# Spring2020V1_7.net
KiCad netlist of a schematic drawn in EAGLE
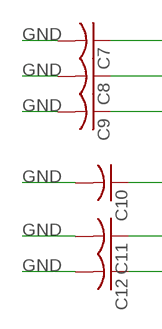
[diagram p0: schematic, sheet 1, part 1 of 2]
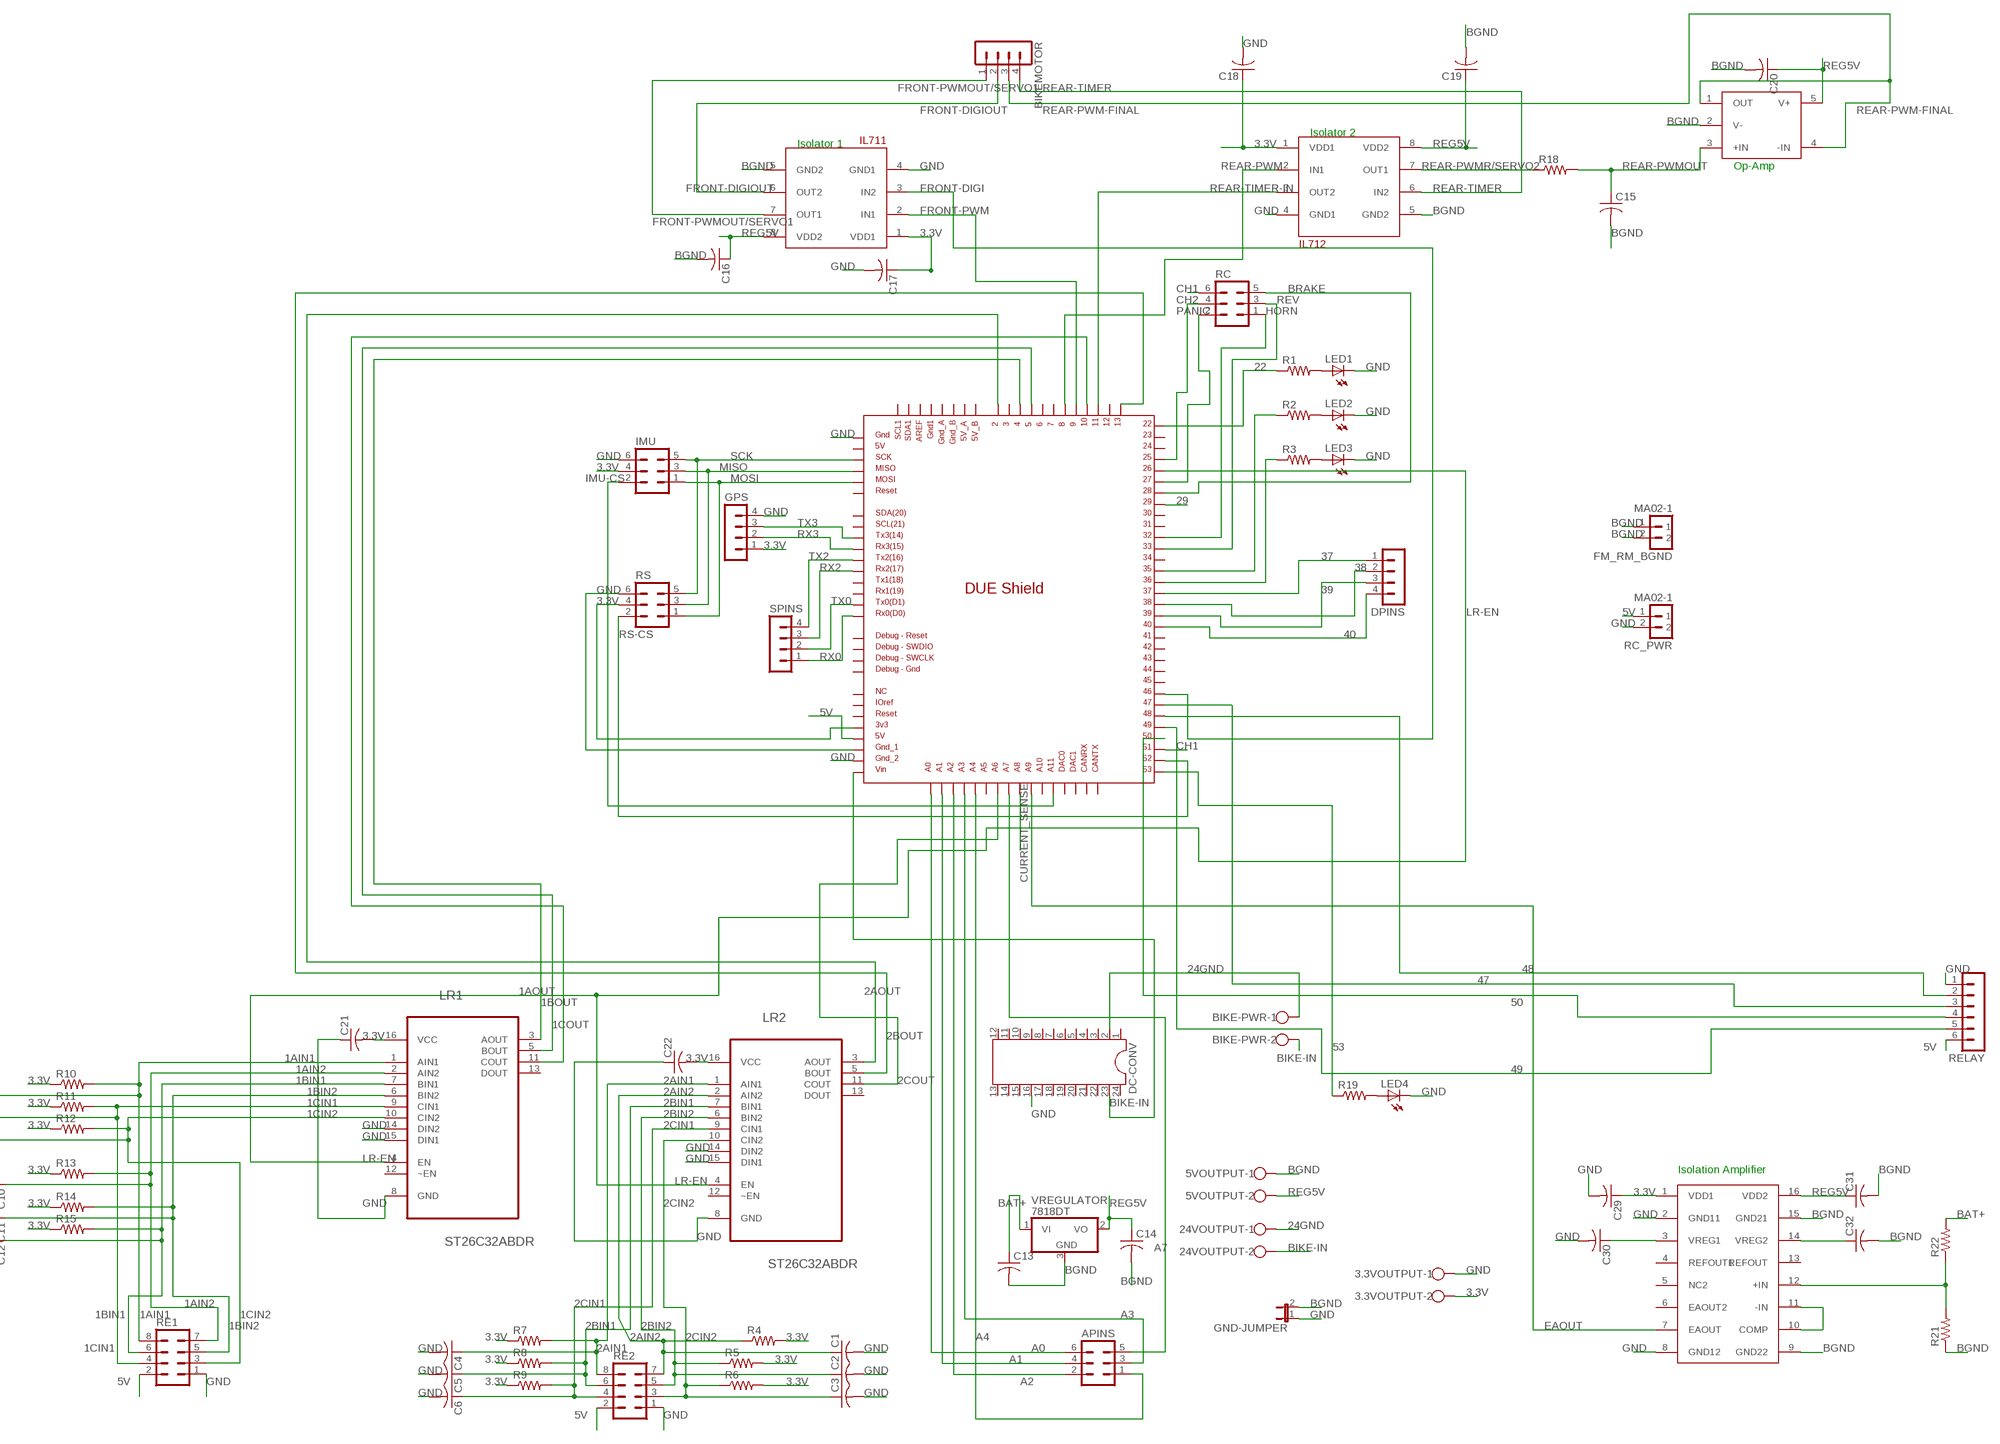
[diagram p1: schematic, sheet 1, part 2 of 2]

(export (version "E")
  (design (tool "Eeschema 10.0.6"))
  (components
    (comp (ref "3.3VOUTPUT")
      (value "W237-102")
      (footprint "eagle-import:W237-102")
      (fields (field (name "MPN") "237-102"))
      (libsource (lib "eagle-import") (part "W237-102"))
    )
    (comp (ref "5VOUTPUT")
      (value "W237-102")
      (footprint "eagle-import:W237-102")
      (fields (field (name "MPN") "237-102"))
      (libsource (lib "eagle-import") (part "W237-102"))
    )
    (comp (ref "24VOUTPUT")
      (value "W237-102")
      (footprint "eagle-import:W237-102")
      (fields (field (name "MPN") "237-102"))
      (libsource (lib "eagle-import") (part "W237-102"))
    )
    (comp (ref "APINS")
      (value "MA03-2")
      (footprint "eagle-import:MA03-2")
      (libsource (lib "eagle-import") (part "MA03-2"))
    )
    (comp (ref "BIKE-PWR")
      (value "W237-102")
      (footprint "eagle-import:W237-102")
      (fields (field (name "MPN") "237-102"))
      (libsource (lib "eagle-import") (part "W237-102"))
    )
    (comp (ref "BIKEMOTOR")
      (value "MA04-1")
      (footprint "eagle-import:MA04-1")
      (libsource (lib "eagle-import") (part "MA04-1"))
    )
    (comp (ref "C1")
      (value "C-US025-025X050")
      (footprint "eagle-import:C025-025X050")
      (libsource (lib "eagle-import") (part "C-US025-025X050"))
    )
    (comp (ref "C2")
      (value "C-US025-025X050")
      (footprint "eagle-import:C025-025X050")
      (libsource (lib "eagle-import") (part "C-US025-025X050"))
    )
    (comp (ref "C3")
      (value "C-US025-025X050")
      (footprint "eagle-import:C025-025X050")
      (libsource (lib "eagle-import") (part "C-US025-025X050"))
    )
    (comp (ref "C4")
      (value "C-US025-025X050")
      (footprint "eagle-import:C025-025X050")
      (libsource (lib "eagle-import") (part "C-US025-025X050"))
    )
    (comp (ref "C5")
      (value "C-US025-025X050")
      (footprint "eagle-import:C025-025X050")
      (libsource (lib "eagle-import") (part "C-US025-025X050"))
    )
    (comp (ref "C6")
      (value "C-US025-025X050")
      (footprint "eagle-import:C025-025X050")
      (libsource (lib "eagle-import") (part "C-US025-025X050"))
    )
    (comp (ref "C7")
      (value "C-US025-025X050")
      (footprint "eagle-import:C025-025X050")
      (libsource (lib "eagle-import") (part "C-US025-025X050"))
    )
    (comp (ref "C8")
      (value "C-US025-025X050")
      (footprint "eagle-import:C025-025X050")
      (libsource (lib "eagle-import") (part "C-US025-025X050"))
    )
    (comp (ref "C9")
      (value "C-US025-025X050")
      (footprint "eagle-import:C025-025X050")
      (libsource (lib "eagle-import") (part "C-US025-025X050"))
    )
    (comp (ref "C10")
      (value "C-US025-025X050")
      (footprint "eagle-import:C025-025X050")
      (libsource (lib "eagle-import") (part "C-US025-025X050"))
    )
    (comp (ref "C11")
      (value "C-US025-025X050")
      (footprint "eagle-import:C025-025X050")
      (libsource (lib "eagle-import") (part "C-US025-025X050"))
    )
    (comp (ref "C12")
      (value "C-US025-025X050")
      (footprint "eagle-import:C025-025X050")
      (libsource (lib "eagle-import") (part "C-US025-025X050"))
    )
    (comp (ref "C13")
      (value "C-US025-050X050")
      (footprint "eagle-import:C025-050X050")
      (libsource (lib "eagle-import") (part "C-US025-050X050"))
    )
    (comp (ref "C14")
      (value "C-US025-050X050")
      (footprint "eagle-import:C025-050X050")
      (libsource (lib "eagle-import") (part "C-US025-050X050"))
    )
    (comp (ref "C15")
      (value "C-US025-050X050")
      (footprint "eagle-import:C025-050X050")
      (libsource (lib "eagle-import") (part "C-US025-050X050"))
    )
    (comp (ref "C16")
      (value "C-US025-050X050")
      (footprint "eagle-import:C025-050X050")
      (libsource (lib "eagle-import") (part "C-US025-050X050"))
    )
    (comp (ref "C17")
      (value "C-US025-050X050")
      (footprint "eagle-import:C025-050X050")
      (libsource (lib "eagle-import") (part "C-US025-050X050"))
    )
    (comp (ref "C18")
      (value "C-US025-050X050")
      (footprint "eagle-import:C025-050X050")
      (libsource (lib "eagle-import") (part "C-US025-050X050"))
    )
    (comp (ref "C19")
      (value "C-US025-050X050")
      (footprint "eagle-import:C025-050X050")
      (libsource (lib "eagle-import") (part "C-US025-050X050"))
    )
    (comp (ref "C20")
      (value "C-US025-050X050")
      (footprint "eagle-import:C025-050X050")
      (libsource (lib "eagle-import") (part "C-US025-050X050"))
    )
    (comp (ref "C21")
      (value "C-US025-050X050")
      (footprint "eagle-import:C025-050X050")
      (libsource (lib "eagle-import") (part "C-US025-050X050"))
    )
    (comp (ref "C22")
      (value "C-US025-050X050")
      (footprint "eagle-import:C025-050X050")
      (libsource (lib "eagle-import") (part "C-US025-050X050"))
    )
    (comp (ref "C29")
      (value "C-US025-050X050")
      (footprint "eagle-import:C025-050X050")
      (libsource (lib "eagle-import") (part "C-US025-050X050"))
    )
    (comp (ref "C30")
      (value "C-US025-050X050")
      (footprint "eagle-import:C025-050X050")
      (libsource (lib "eagle-import") (part "C-US025-050X050"))
    )
    (comp (ref "C31")
      (value "C-US025-050X050")
      (footprint "eagle-import:C025-050X050")
      (libsource (lib "eagle-import") (part "C-US025-050X050"))
    )
    (comp (ref "C32")
      (value "C-US025-050X050")
      (footprint "eagle-import:C025-050X050")
      (libsource (lib "eagle-import") (part "C-US025-050X050"))
    )
    (comp (ref "DC-CONV")
      (value "CU.INC---VAWQ6-Q48-S12H-6")
      (footprint "eagle-import:DIL24-6")
      (libsource (lib "eagle-import") (part "CU.INC---VAWQ6-Q48-S12H-6"))
    )
    (comp (ref "DPINS")
      (value "MA04-1")
      (footprint "eagle-import:MA04-1")
      (libsource (lib "eagle-import") (part "MA04-1"))
    )
    (comp (ref "FM_RM_BGND")
      (value "MA02-1")
      (footprint "eagle-import:MA02-1")
      (libsource (lib "eagle-import") (part "MA02-1"))
    )
    (comp (ref "GND-JUMPER")
      (value "JP1E")
      (footprint "eagle-import:JP1")
      (libsource (lib "eagle-import") (part "JP1E"))
    )
    (comp (ref "GPS")
      (value "MA04-1")
      (footprint "eagle-import:MA04-1")
      (libsource (lib "eagle-import") (part "MA04-1"))
    )
    (comp (ref "IMU")
      (value "MA03-2")
      (footprint "eagle-import:MA03-2")
      (libsource (lib "eagle-import") (part "MA03-2"))
    )
    (comp (ref "LED1")
      (value "LED5MM")
      (footprint "eagle-import:LED5MM")
      (libsource (lib "eagle-import") (part "LED5MM"))
    )
    (comp (ref "LED2")
      (value "LED5MM")
      (footprint "eagle-import:LED5MM")
      (libsource (lib "eagle-import") (part "LED5MM"))
    )
    (comp (ref "LED3")
      (value "LED5MM")
      (footprint "eagle-import:LED5MM")
      (libsource (lib "eagle-import") (part "LED5MM"))
    )
    (comp (ref "LED4")
      (value "LED5MM")
      (footprint "eagle-import:LED5MM")
      (libsource (lib "eagle-import") (part "LED5MM"))
    )
    (comp (ref "LR1")
      (value "ST26C32ABDR")
      (footprint "eagle-import:SOIC127P600X175-16N")
      (libsource (lib "eagle-import") (part "ST26C32ABDR"))
    )
    (comp (ref "LR2")
      (value "ST26C32ABDR")
      (footprint "eagle-import:SOIC127P600X175-16N")
      (libsource (lib "eagle-import") (part "ST26C32ABDR"))
    )
    (comp (ref "OP-AMP")
      (value "OPAMP")
      (footprint "eagle-import:SOT95P280X145-5N")
      (libsource (lib "eagle-import") (part "OPAMP"))
    )
    (comp (ref "R1")
      (value "R-US_0309/10")
      (footprint "eagle-import:0309_10")
      (libsource (lib "eagle-import") (part "R-US_0309/10"))
    )
    (comp (ref "R2")
      (value "R-US_0309/10")
      (footprint "eagle-import:0309_10")
      (libsource (lib "eagle-import") (part "R-US_0309/10"))
    )
    (comp (ref "R3")
      (value "R-US_0309/10")
      (footprint "eagle-import:0309_10")
      (libsource (lib "eagle-import") (part "R-US_0309/10"))
    )
    (comp (ref "R4")
      (value "R-US_0613/15")
      (footprint "eagle-import:P0613_15")
      (libsource (lib "eagle-import") (part "resistor_R-US_0613/15"))
    )
    (comp (ref "R5")
      (value "R-US_0613/15")
      (footprint "eagle-import:P0613_15")
      (libsource (lib "eagle-import") (part "resistor_R-US_0613/15"))
    )
    (comp (ref "R6")
      (value "R-US_0613/15")
      (footprint "eagle-import:P0613_15")
      (libsource (lib "eagle-import") (part "resistor_R-US_0613/15"))
    )
    (comp (ref "R7")
      (value "R-US_0613/15")
      (footprint "eagle-import:P0613_15")
      (libsource (lib "eagle-import") (part "resistor_R-US_0613/15"))
    )
    (comp (ref "R8")
      (value "R-US_0613/15")
      (footprint "eagle-import:P0613_15")
      (libsource (lib "eagle-import") (part "resistor_R-US_0613/15"))
    )
    (comp (ref "R9")
      (value "R-US_0613/15")
      (footprint "eagle-import:P0613_15")
      (libsource (lib "eagle-import") (part "resistor_R-US_0613/15"))
    )
    (comp (ref "R10")
      (value "R-US_0613/15")
      (footprint "eagle-import:P0613_15")
      (libsource (lib "eagle-import") (part "resistor_R-US_0613/15"))
    )
    (comp (ref "R11")
      (value "R-US_0613/15")
      (footprint "eagle-import:P0613_15")
      (libsource (lib "eagle-import") (part "resistor_R-US_0613/15"))
    )
    (comp (ref "R12")
      (value "R-US_0613/15")
      (footprint "eagle-import:P0613_15")
      (libsource (lib "eagle-import") (part "resistor_R-US_0613/15"))
    )
    (comp (ref "R13")
      (value "R-US_0613/15")
      (footprint "eagle-import:P0613_15")
      (libsource (lib "eagle-import") (part "resistor_R-US_0613/15"))
    )
    (comp (ref "R14")
      (value "R-US_0613/15")
      (footprint "eagle-import:P0613_15")
      (libsource (lib "eagle-import") (part "resistor_R-US_0613/15"))
    )
    (comp (ref "R15")
      (value "R-US_0613/15")
      (footprint "eagle-import:P0613_15")
      (libsource (lib "eagle-import") (part "resistor_R-US_0613/15"))
    )
    (comp (ref "R18")
      (value "R-US_0414/15")
      (footprint "eagle-import:0414_15")
      (libsource (lib "eagle-import") (part "resistor_R-US_0414/15"))
    )
    (comp (ref "R19")
      (value "R-US_0309/10")
      (footprint "eagle-import:0309_10")
      (libsource (lib "eagle-import") (part "R-US_0309/10"))
    )
    (comp (ref "R21")
      (value "R-US_0414/15")
      (footprint "eagle-import:0414_15")
      (libsource (lib "eagle-import") (part "resistor_R-US_0414/15"))
    )
    (comp (ref "R22")
      (value "R-US_0414/15")
      (footprint "eagle-import:0414_15")
      (libsource (lib "eagle-import") (part "resistor_R-US_0414/15"))
    )
    (comp (ref "RC")
      (value "MA03-2")
      (footprint "eagle-import:MA03-2")
      (libsource (lib "eagle-import") (part "MA03-2"))
    )
    (comp (ref "RC_PWR")
      (value "MA02-1")
      (footprint "eagle-import:MA02-1")
      (libsource (lib "eagle-import") (part "MA02-1"))
    )
    (comp (ref "RE1")
      (value "MA04-2")
      (footprint "eagle-import:MA04-2")
      (libsource (lib "eagle-import") (part "MA04-2"))
    )
    (comp (ref "RE2")
      (value "MA04-2")
      (footprint "eagle-import:MA04-2")
      (libsource (lib "eagle-import") (part "MA04-2"))
    )
    (comp (ref "RELAY")
      (value "MA06-1")
      (footprint "eagle-import:MA06-1")
      (libsource (lib "eagle-import") (part "MA06-1"))
    )
    (comp (ref "RS")
      (value "MA03-2")
      (footprint "eagle-import:MA03-2")
      (libsource (lib "eagle-import") (part "MA03-2"))
    )
    (comp (ref "SPINS")
      (value "MA04-1")
      (footprint "eagle-import:MA04-1")
      (libsource (lib "eagle-import") (part "MA04-1"))
    )
    (comp (ref "U$1")
      (value "DUE(NORMAL)")
      (footprint "eagle-import:DUE(NORMAL)")
      (libsource (lib "eagle-import") (part "DUE(NORMAL)"))
    )
    (comp (ref "U$2")
      (value "IL-711")
      (footprint "eagle-import:8PINSOIC")
      (libsource (lib "eagle-import") (part "IL-711"))
    )
    (comp (ref "U$5")
      (value "ISOLATED_ERROR_AMP_ADUM3190")
      (footprint "eagle-import:QSOP16")
      (libsource (lib "eagle-import") (part "ISOLATED_ERROR_AMP_ADUM3190"))
    )
    (comp (ref "U$7")
      (value "IL-712")
      (footprint "eagle-import:8PINSOIC")
      (libsource (lib "eagle-import") (part "IL-712"))
    )
    (comp (ref "VREGULATOR")
      (value "7818DT")
      (footprint "eagle-import:TO252")
      (libsource (lib "eagle-import") (part "78DT18"))
    )
  )
  (nets
    (net (code "1") (name "/1AIN1") (class "Default")
      (node (ref "C7") (pin "1") (pinfunction "1_1") (pintype "passive"))
      (node (ref "LR1") (pin "1") (pinfunction "AIN1_1") (pintype "input"))
      (node (ref "R10") (pin "2") (pinfunction "2_2") (pintype "passive"))
      (node (ref "RE1") (pin "8") (pinfunction "8_8") (pintype "passive"))
    )
    (net (code "2") (name "/1AIN2") (class "Default")
      (node (ref "C10") (pin "1") (pinfunction "1_1") (pintype "passive"))
      (node (ref "LR1") (pin "2") (pinfunction "AIN2_2") (pintype "input"))
      (node (ref "R13") (pin "2") (pinfunction "2_2") (pintype "passive"))
      (node (ref "RE1") (pin "7") (pinfunction "7_7") (pintype "passive"))
    )
    (net (code "3") (name "/1AOUT") (class "Default")
      (node (ref "LR1") (pin "3") (pinfunction "AOUT_3") (pintype "output"))
      (node (ref "U$1") (pin "4") (pinfunction "4_4") (pintype "bidirectional"))
    )
    (net (code "4") (name "/1BIN1") (class "Default")
      (node (ref "C12") (pin "1") (pinfunction "1_1") (pintype "passive"))
      (node (ref "LR1") (pin "7") (pinfunction "BIN1_7") (pintype "input"))
      (node (ref "R15") (pin "2") (pinfunction "2_2") (pintype "passive"))
      (node (ref "RE1") (pin "6") (pinfunction "6_6") (pintype "passive"))
    )
    (net (code "5") (name "/1BIN2") (class "Default")
      (node (ref "C11") (pin "1") (pinfunction "1_1") (pintype "passive"))
      (node (ref "LR1") (pin "6") (pinfunction "BIN2_6") (pintype "input"))
      (node (ref "R14") (pin "2") (pinfunction "2_2") (pintype "passive"))
      (node (ref "RE1") (pin "5") (pinfunction "5_5") (pintype "passive"))
    )
    (net (code "6") (name "/1BOUT") (class "Default")
      (node (ref "LR1") (pin "5") (pinfunction "BOUT_5") (pintype "output"))
      (node (ref "U$1") (pin "5") (pinfunction "5_5") (pintype "bidirectional"))
    )
    (net (code "7") (name "/1CIN1") (class "Default")
      (node (ref "C8") (pin "1") (pinfunction "1_1") (pintype "passive"))
      (node (ref "LR1") (pin "9") (pinfunction "CIN1_9") (pintype "input"))
      (node (ref "R11") (pin "2") (pinfunction "2_2") (pintype "passive"))
      (node (ref "RE1") (pin "4") (pinfunction "4_4") (pintype "passive"))
    )
    (net (code "8") (name "/1CIN2") (class "Default")
      (node (ref "C9") (pin "1") (pinfunction "1_1") (pintype "passive"))
      (node (ref "LR1") (pin "10") (pinfunction "CIN2_10") (pintype "input"))
      (node (ref "R12") (pin "2") (pinfunction "2_2") (pintype "passive"))
      (node (ref "RE1") (pin "3") (pinfunction "3_3") (pintype "passive"))
    )
    (net (code "9") (name "/1COUT") (class "Default")
      (node (ref "LR1") (pin "11") (pinfunction "COUT_11") (pintype "output"))
      (node (ref "U$1") (pin "10") (pinfunction "10_10") (pintype "bidirectional"))
    )
    (net (code "10") (name "/2AIN1") (class "Default")
      (node (ref "C4") (pin "1") (pinfunction "1_1") (pintype "passive"))
      (node (ref "LR2") (pin "1") (pinfunction "AIN1_1") (pintype "input"))
      (node (ref "R7") (pin "2") (pinfunction "2_2") (pintype "passive"))
      (node (ref "RE2") (pin "8") (pinfunction "8_8") (pintype "passive"))
    )
    (net (code "11") (name "/2AIN2") (class "Default")
      (node (ref "C1") (pin "1") (pinfunction "1_1") (pintype "passive"))
      (node (ref "LR2") (pin "2") (pinfunction "AIN2_2") (pintype "input"))
      (node (ref "R4") (pin "1") (pinfunction "1_1") (pintype "passive"))
      (node (ref "RE2") (pin "7") (pinfunction "7_7") (pintype "passive"))
    )
    (net (code "12") (name "/2AOUT") (class "Default")
      (node (ref "LR2") (pin "3") (pinfunction "AOUT_3") (pintype "output"))
      (node (ref "U$1") (pin "2") (pinfunction "2_2") (pintype "bidirectional"))
    )
    (net (code "13") (name "/2BIN1") (class "Default")
      (node (ref "C5") (pin "1") (pinfunction "1_1") (pintype "passive"))
      (node (ref "LR2") (pin "7") (pinfunction "BIN1_7") (pintype "input"))
      (node (ref "R8") (pin "2") (pinfunction "2_2") (pintype "passive"))
      (node (ref "RE2") (pin "6") (pinfunction "6_6") (pintype "passive"))
    )
    (net (code "14") (name "/2BIN2") (class "Default")
      (node (ref "C2") (pin "1") (pinfunction "1_1") (pintype "passive"))
      (node (ref "LR2") (pin "6") (pinfunction "BIN2_6") (pintype "input"))
      (node (ref "R5") (pin "1") (pinfunction "1_1") (pintype "passive"))
      (node (ref "RE2") (pin "5") (pinfunction "5_5") (pintype "passive"))
    )
    (net (code "15") (name "/2BOUT") (class "Default")
      (node (ref "LR2") (pin "5") (pinfunction "BOUT_5") (pintype "output"))
      (node (ref "U$1") (pin "13") (pinfunction "13_13") (pintype "bidirectional"))
    )
    (net (code "16") (name "/2CIN1") (class "Default")
      (node (ref "C6") (pin "1") (pinfunction "1_1") (pintype "passive"))
      (node (ref "LR2") (pin "9") (pinfunction "CIN1_9") (pintype "input"))
      (node (ref "R9") (pin "2") (pinfunction "2_2") (pintype "passive"))
      (node (ref "RE2") (pin "4") (pinfunction "4_4") (pintype "passive"))
    )
    (net (code "17") (name "/2CIN2") (class "Default")
      (node (ref "C3") (pin "1") (pinfunction "1_1") (pintype "passive"))
      (node (ref "LR2") (pin "10") (pinfunction "CIN2_10") (pintype "input"))
      (node (ref "R6") (pin "1") (pinfunction "1_1") (pintype "passive"))
      (node (ref "RE2") (pin "3") (pinfunction "3_3") (pintype "passive"))
    )
    (net (code "18") (name "/2COUT") (class "Default")
      (node (ref "LR2") (pin "11") (pinfunction "COUT_11") (pintype "output"))
      (node (ref "U$1") (pin "A6") (pinfunction "A6_A6") (pintype "bidirectional"))
    )
    (net (code "19") (name "/3.3V") (class "Default")
      (node (ref "3.3VOUTPUT") (pin "2") (pinfunction "KL_2") (pintype "passive"))
      (node (ref "C17") (pin "1") (pinfunction "1_1") (pintype "passive"))
      (node (ref "C18") (pin "1") (pinfunction "1_1") (pintype "passive"))
      (node (ref "C21") (pin "2") (pinfunction "2_2") (pintype "passive"))
      (node (ref "C22") (pin "2") (pinfunction "2_2") (pintype "passive"))
      (node (ref "C29") (pin "1") (pinfunction "1_1") (pintype "passive"))
      (node (ref "GPS") (pin "1") (pinfunction "1_1") (pintype "passive"))
      (node (ref "IMU") (pin "4") (pinfunction "4_4") (pintype "passive"))
      (node (ref "LR1") (pin "16") (pinfunction "VCC_16") (pintype "power_in"))
      (node (ref "LR2") (pin "16") (pinfunction "VCC_16") (pintype "power_in"))
      (node (ref "R10") (pin "1") (pinfunction "1_1") (pintype "passive"))
      (node (ref "R11") (pin "1") (pinfunction "1_1") (pintype "passive"))
      (node (ref "R12") (pin "1") (pinfunction "1_1") (pintype "passive"))
      (node (ref "R13") (pin "1") (pinfunction "1_1") (pintype "passive"))
      (node (ref "R14") (pin "1") (pinfunction "1_1") (pintype "passive"))
      (node (ref "R15") (pin "1") (pinfunction "1_1") (pintype "passive"))
      (node (ref "R4") (pin "2") (pinfunction "2_2") (pintype "passive"))
      (node (ref "R5") (pin "2") (pinfunction "2_2") (pintype "passive"))
      (node (ref "R6") (pin "2") (pinfunction "2_2") (pintype "passive"))
      (node (ref "R7") (pin "1") (pinfunction "1_1") (pintype "passive"))
      (node (ref "R8") (pin "1") (pinfunction "1_1") (pintype "passive"))
      (node (ref "R9") (pin "1") (pinfunction "1_1") (pintype "passive"))
      (node (ref "RS") (pin "4") (pinfunction "4_4") (pintype "passive"))
      (node (ref "U$1") (pin "3V3") (pinfunction "3V3_3V3") (pintype "bidirectional"))
      (node (ref "U$2") (pin "1") (pinfunction "VDD1_1") (pintype "power_in"))
      (node (ref "U$5") (pin "1") (pinfunction "VDD1_1") (pintype "bidirectional"))
      (node (ref "U$7") (pin "1") (pinfunction "VDD1_1") (pintype "power_in"))
    )
    (net (code "20") (name "/5V") (class "Default")
      (node (ref "RC_PWR") (pin "1") (pinfunction "1_1") (pintype "passive"))
      (node (ref "RE1") (pin "2") (pinfunction "2_2") (pintype "passive"))
      (node (ref "RE2") (pin "2") (pinfunction "2_2") (pintype "passive"))
      (node (ref "RELAY") (pin "6") (pinfunction "6_6") (pintype "passive"))
      (node (ref "U$1") (pin "5V") (pinfunction "5V_5V") (pintype "bidirectional"))
    )
    (net (code "21") (name "/22") (class "Default")
      (node (ref "R1") (pin "1") (pinfunction "1_1") (pintype "passive"))
      (node (ref "U$1") (pin "22") (pinfunction "22_22") (pintype "bidirectional"))
    )
    (net (code "22") (name "/24GND") (class "Default")
      (node (ref "24VOUTPUT") (pin "1") (pinfunction "KL_1") (pintype "passive"))
      (node (ref "BIKE-PWR") (pin "1") (pinfunction "KL_1") (pintype "passive"))
      (node (ref "DC-CONV") (pin "2") (pinfunction "2_2") (pintype "passive"))
    )
    (net (code "23") (name "/29") (class "Default")
      (node (ref "U$1") (pin "29") (pinfunction "29_29") (pintype "bidirectional"))
    )
    (net (code "24") (name "/37") (class "Default")
      (node (ref "DPINS") (pin "1") (pinfunction "1_1") (pintype "passive"))
      (node (ref "U$1") (pin "37") (pinfunction "37_37") (pintype "bidirectional"))
    )
    (net (code "25") (name "/38") (class "Default")
      (node (ref "DPINS") (pin "2") (pinfunction "2_2") (pintype "passive"))
      (node (ref "U$1") (pin "38") (pinfunction "38_38") (pintype "bidirectional"))
    )
    (net (code "26") (name "/39") (class "Default")
      (node (ref "DPINS") (pin "3") (pinfunction "3_3") (pintype "passive"))
      (node (ref "U$1") (pin "39") (pinfunction "39_39") (pintype "bidirectional"))
    )
    (net (code "27") (name "/40") (class "Default")
      (node (ref "DPINS") (pin "4") (pinfunction "4_4") (pintype "passive"))
      (node (ref "U$1") (pin "40") (pinfunction "40_40") (pintype "bidirectional"))
    )
    (net (code "28") (name "/47") (class "Default")
      (node (ref "RELAY") (pin "3") (pinfunction "3_3") (pintype "passive"))
      (node (ref "U$1") (pin "47") (pinfunction "47_47") (pintype "bidirectional"))
    )
    (net (code "29") (name "/48") (class "Default")
      (node (ref "RELAY") (pin "2") (pinfunction "2_2") (pintype "passive"))
      (node (ref "U$1") (pin "48") (pinfunction "48_48") (pintype "bidirectional"))
    )
    (net (code "30") (name "/49") (class "Default")
      (node (ref "RELAY") (pin "5") (pinfunction "5_5") (pintype "passive"))
      (node (ref "U$1") (pin "49") (pinfunction "49_49") (pintype "bidirectional"))
    )
    (net (code "31") (name "/50") (class "Default")
      (node (ref "RELAY") (pin "4") (pinfunction "4_4") (pintype "passive"))
      (node (ref "U$1") (pin "50") (pinfunction "50_50") (pintype "bidirectional"))
    )
    (net (code "32") (name "/53") (class "Default")
      (node (ref "R19") (pin "1") (pinfunction "1_1") (pintype "passive"))
      (node (ref "U$1") (pin "53") (pinfunction "53_53") (pintype "bidirectional"))
    )
    (net (code "33") (name "/A0") (class "Default")
      (node (ref "APINS") (pin "6") (pinfunction "6_6") (pintype "passive"))
      (node (ref "U$1") (pin "A0") (pinfunction "A0_A0") (pintype "bidirectional"))
    )
    (net (code "34") (name "/A1") (class "Default")
      (node (ref "APINS") (pin "4") (pinfunction "4_4") (pintype "passive"))
      (node (ref "U$1") (pin "A1") (pinfunction "A1_A1") (pintype "bidirectional"))
    )
    (net (code "35") (name "/A2") (class "Default")
      (node (ref "APINS") (pin "2") (pinfunction "2_2") (pintype "passive"))
      (node (ref "U$1") (pin "A2") (pinfunction "A2_A2") (pintype "bidirectional"))
    )
    (net (code "36") (name "/A3") (class "Default")
      (node (ref "APINS") (pin "3") (pinfunction "3_3") (pintype "passive"))
      (node (ref "U$1") (pin "A3") (pinfunction "A3_A3") (pintype "bidirectional"))
    )
    (net (code "37") (name "/A4") (class "Default")
      (node (ref "APINS") (pin "1") (pinfunction "1_1") (pintype "passive"))
      (node (ref "U$1") (pin "A4") (pinfunction "A4_A4") (pintype "bidirectional"))
    )
    (net (code "38") (name "/A7") (class "Default")
      (node (ref "APINS") (pin "5") (pinfunction "5_5") (pintype "passive"))
      (node (ref "U$1") (pin "A7") (pinfunction "A7_A7") (pintype "bidirectional"))
    )
    (net (code "39") (name "/BAT+") (class "Default")
      (node (ref "C13") (pin "1") (pinfunction "1_1") (pintype "passive"))
      (node (ref "R22") (pin "2") (pinfunction "2_2") (pintype "passive"))
      (node (ref "VREGULATOR") (pin "1") (pinfunction "VI_1") (pintype "input"))
    )
    (net (code "40") (name "/BGND") (class "Default")
      (node (ref "5VOUTPUT") (pin "1") (pinfunction "KL_1") (pintype "passive"))
      (node (ref "C13") (pin "2") (pinfunction "2_2") (pintype "passive"))
      (node (ref "C14") (pin "2") (pinfunction "2_2") (pintype "passive"))
      (node (ref "C15") (pin "2") (pinfunction "2_2") (pintype "passive"))
      (node (ref "C16") (pin "2") (pinfunction "2_2") (pintype "passive"))
      (node (ref "C19") (pin "2") (pinfunction "2_2") (pintype "passive"))
      (node (ref "C20") (pin "2") (pinfunction "2_2") (pintype "passive"))
      (node (ref "C31") (pin "2") (pinfunction "2_2") (pintype "passive"))
      (node (ref "C32") (pin "2") (pinfunction "2_2") (pintype "passive"))
      (node (ref "FM_RM_BGND") (pin "1") (pinfunction "1_1") (pintype "passive"))
      (node (ref "FM_RM_BGND") (pin "2") (pinfunction "2_2") (pintype "passive"))
      (node (ref "GND-JUMPER") (pin "2") (pinfunction "2_2") (pintype "passive"))
      (node (ref "OP-AMP") (pin "2") (pinfunction "V-_2") (pintype "output"))
      (node (ref "R21") (pin "1") (pinfunction "1_1") (pintype "passive"))
      (node (ref "U$2") (pin "5") (pinfunction "GND2_5") (pintype "power_in"))
      (node (ref "U$5") (pin "15") (pinfunction "GND21_15") (pintype "bidirectional"))
      (node (ref "U$5") (pin "9") (pinfunction "GND22_9") (pintype "bidirectional"))
      (node (ref "U$7") (pin "5") (pinfunction "GND2_5") (pintype "power_in"))
      (node (ref "VREGULATOR") (pin "3") (pinfunction "GND_3") (pintype "passive"))
    )
    (net (code "41") (name "/BIKE-IN") (class "Default")
      (node (ref "24VOUTPUT") (pin "2") (pinfunction "KL_2") (pintype "passive"))
      (node (ref "BIKE-PWR") (pin "2") (pinfunction "KL_2") (pintype "passive"))
      (node (ref "DC-CONV") (pin "23") (pinfunction "23_23") (pintype "passive"))
      (node (ref "U$1") (pin "VIN") (pinfunction "VIN_VIN") (pintype "bidirectional"))
    )
    (net (code "42") (name "/BRAKE") (class "Default")
      (node (ref "RC") (pin "5") (pinfunction "5_5") (pintype "passive"))
      (node (ref "U$1") (pin "28") (pinfunction "28_28") (pintype "bidirectional"))
    )
    (net (code "43") (name "/CH1") (class "Default")
      (node (ref "RC") (pin "6") (pinfunction "6_6") (pintype "passive"))
      (node (ref "U$1") (pin "51") (pinfunction "51_51") (pintype "bidirectional"))
    )
    (net (code "44") (name "/CH2") (class "Default")
      (node (ref "RC") (pin "4") (pinfunction "4_4") (pintype "passive"))
      (node (ref "U$1") (pin "25") (pinfunction "25_25") (pintype "bidirectional"))
    )
    (net (code "45") (name "/CURRENT_SENSE") (class "Default")
      (node (ref "U$1") (pin "A8") (pinfunction "A8_A8") (pintype "bidirectional"))
    )
    (net (code "46") (name "/EAOUT") (class "Default")
      (node (ref "U$1") (pin "A9") (pinfunction "A9_A9") (pintype "bidirectional"))
      (node (ref "U$5") (pin "7") (pinfunction "EAOUT_7") (pintype "bidirectional"))
    )
    (net (code "47") (name "/FRONT-DIGI") (class "Default")
      (node (ref "U$1") (pin "46") (pinfunction "46_46") (pintype "bidirectional"))
      (node (ref "U$2") (pin "3") (pinfunction "IN2_3") (pintype "input"))
    )
    (net (code "48") (name "/FRONT-DIGIOUT") (class "Default")
      (node (ref "BIKEMOTOR") (pin "2") (pinfunction "2_2") (pintype "passive"))
      (node (ref "U$2") (pin "6") (pinfunction "OUT2_6") (pintype "output"))
    )
    (net (code "49") (name "/FRONT-PWM") (class "Default")
      (node (ref "U$1") (pin "9") (pinfunction "9_9") (pintype "bidirectional"))
      (node (ref "U$2") (pin "2") (pinfunction "IN1_2") (pintype "input"))
    )
    (net (code "50") (name "/FRONT-PWMOUT{slash}SERVO1") (class "Default")
      (node (ref "BIKEMOTOR") (pin "1") (pinfunction "1_1") (pintype "passive"))
      (node (ref "U$2") (pin "7") (pinfunction "OUT1_7") (pintype "output"))
    )
    (net (code "51") (name "/GND") (class "Default")
      (node (ref "3.3VOUTPUT") (pin "1") (pinfunction "KL_1") (pintype "passive"))
      (node (ref "C1") (pin "2") (pinfunction "2_2") (pintype "passive"))
      (node (ref "C10") (pin "2") (pinfunction "2_2") (pintype "passive"))
      (node (ref "C11") (pin "2") (pinfunction "2_2") (pintype "passive"))
      (node (ref "C12") (pin "2") (pinfunction "2_2") (pintype "passive"))
      (node (ref "C17") (pin "2") (pinfunction "2_2") (pintype "passive"))
      (node (ref "C18") (pin "2") (pinfunction "2_2") (pintype "passive"))
      (node (ref "C2") (pin "2") (pinfunction "2_2") (pintype "passive"))
      (node (ref "C21") (pin "1") (pinfunction "1_1") (pintype "passive"))
      (node (ref "C22") (pin "1") (pinfunction "1_1") (pintype "passive"))
      (node (ref "C29") (pin "2") (pinfunction "2_2") (pintype "passive"))
      (node (ref "C3") (pin "2") (pinfunction "2_2") (pintype "passive"))
      (node (ref "C30") (pin "2") (pinfunction "2_2") (pintype "passive"))
      (node (ref "C4") (pin "2") (pinfunction "2_2") (pintype "passive"))
      (node (ref "C5") (pin "2") (pinfunction "2_2") (pintype "passive"))
      (node (ref "C6") (pin "2") (pinfunction "2_2") (pintype "passive"))
      (node (ref "C7") (pin "2") (pinfunction "2_2") (pintype "passive"))
      (node (ref "C8") (pin "2") (pinfunction "2_2") (pintype "passive"))
      (node (ref "C9") (pin "2") (pinfunction "2_2") (pintype "passive"))
      (node (ref "DC-CONV") (pin "16") (pinfunction "16_16") (pintype "passive"))
      (node (ref "GND-JUMPER") (pin "1") (pinfunction "1_1") (pintype "passive"))
      (node (ref "GPS") (pin "4") (pinfunction "4_4") (pintype "passive"))
      (node (ref "IMU") (pin "6") (pinfunction "6_6") (pintype "passive"))
      (node (ref "LED1") (pin "K") (pinfunction "C_K") (pintype "passive"))
      (node (ref "LED2") (pin "K") (pinfunction "C_K") (pintype "passive"))
      (node (ref "LED3") (pin "K") (pinfunction "C_K") (pintype "passive"))
      (node (ref "LED4") (pin "K") (pinfunction "C_K") (pintype "passive"))
      (node (ref "LR1") (pin "14") (pinfunction "DIN2_14") (pintype "input"))
      (node (ref "LR1") (pin "15") (pinfunction "DIN1_15") (pintype "input"))
      (node (ref "LR1") (pin "8") (pinfunction "GND_8") (pintype "passive"))
      (node (ref "LR2") (pin "14") (pinfunction "DIN2_14") (pintype "input"))
      (node (ref "LR2") (pin "15") (pinfunction "DIN1_15") (pintype "input"))
      (node (ref "LR2") (pin "8") (pinfunction "GND_8") (pintype "passive"))
      (node (ref "RC_PWR") (pin "2") (pinfunction "2_2") (pintype "passive"))
      (node (ref "RE1") (pin "1") (pinfunction "1_1") (pintype "passive"))
      (node (ref "RE2") (pin "1") (pinfunction "1_1") (pintype "passive"))
      (node (ref "RELAY") (pin "1") (pinfunction "1_1") (pintype "passive"))
      (node (ref "RS") (pin "6") (pinfunction "6_6") (pintype "passive"))
      (node (ref "U$1") (pin "5V_ICSP") (pinfunction "5V_ICSP_5V_ICSP") (pintype "bidirectional"))
      (node (ref "U$1") (pin "GND_1") (pinfunction "GND_1_GND_1") (pintype "bidirectional"))
      (node (ref "U$1") (pin "GND_2") (pinfunction "GND_2_GND_2") (pintype "bidirectional"))
      (node (ref "U$2") (pin "4") (pinfunction "GND1_4") (pintype "power_in"))
      (node (ref "U$5") (pin "2") (pinfunction "GND11_2") (pintype "bidirectional"))
      (node (ref "U$5") (pin "8") (pinfunction "GND12_8") (pintype "bidirectional"))
      (node (ref "U$7") (pin "4") (pinfunction "GND1_4") (pintype "power_in"))
    )
    (net (code "52") (name "/HORN") (class "Default")
      (node (ref "RC") (pin "1") (pinfunction "1_1") (pintype "passive"))
      (node (ref "U$1") (pin "32") (pinfunction "32_32") (pintype "bidirectional"))
    )
    (net (code "53") (name "/IMU-CS") (class "Default")
      (node (ref "IMU") (pin "2") (pinfunction "2_2") (pintype "passive"))
      (node (ref "U$1") (pin "A11") (pinfunction "A11_A11") (pintype "bidirectional"))
    )
    (net (code "54") (name "/LR-EN") (class "Default")
      (node (ref "LR1") (pin "4") (pinfunction "EN_4") (pintype "input"))
      (node (ref "LR2") (pin "4") (pinfunction "EN_4") (pintype "input"))
      (node (ref "U$1") (pin "26") (pinfunction "26_26") (pintype "bidirectional"))
    )
    (net (code "55") (name "/MISO") (class "Default")
      (node (ref "IMU") (pin "3") (pinfunction "3_3") (pintype "passive"))
      (node (ref "RS") (pin "3") (pinfunction "3_3") (pintype "passive"))
      (node (ref "U$1") (pin "MISO_ICSP") (pinfunction "MISO_ICSP_MISO_ICSP") (pintype "bidirectional"))
    )
    (net (code "56") (name "/MOSI") (class "Default")
      (node (ref "IMU") (pin "1") (pinfunction "1_1") (pintype "passive"))
      (node (ref "RS") (pin "1") (pinfunction "1_1") (pintype "passive"))
      (node (ref "U$1") (pin "MOSI_ICSP") (pinfunction "MOSI_ICSP_MOSI_ICSP") (pintype "bidirectional"))
    )
    (net (code "57") (name "/PANIC") (class "Default")
      (node (ref "RC") (pin "2") (pinfunction "2_2") (pintype "passive"))
      (node (ref "U$1") (pin "27") (pinfunction "27_27") (pintype "bidirectional"))
    )
    (net (code "58") (name "/REAR-PWM") (class "Default")
      (node (ref "U$1") (pin "8") (pinfunction "8_8") (pintype "bidirectional"))
      (node (ref "U$7") (pin "2") (pinfunction "IN1_2") (pintype "input"))
    )
    (net (code "59") (name "/REAR-PWM-FINAL") (class "Default")
      (node (ref "BIKEMOTOR") (pin "3") (pinfunction "3_3") (pintype "passive"))
      (node (ref "OP-AMP") (pin "1") (pinfunction "OUT_1") (pintype "output"))
      (node (ref "OP-AMP") (pin "4") (pinfunction "-IN_4") (pintype "input"))
    )
    (net (code "60") (name "/REAR-PWMOUT") (class "Default")
      (node (ref "C15") (pin "1") (pinfunction "1_1") (pintype "passive"))
      (node (ref "OP-AMP") (pin "3") (pinfunction "+IN_3") (pintype "input"))
      (node (ref "R18") (pin "2") (pinfunction "2_2") (pintype "passive"))
    )
    (net (code "61") (name "/REAR-PWMR{slash}SERVO2") (class "Default")
      (node (ref "R18") (pin "1") (pinfunction "1_1") (pintype "passive"))
      (node (ref "U$7") (pin "7") (pinfunction "OUT1_7") (pintype "output"))
    )
    (net (code "62") (name "/REAR-TIMER") (class "Default")
      (node (ref "BIKEMOTOR") (pin "4") (pinfunction "4_4") (pintype "passive"))
      (node (ref "U$7") (pin "6") (pinfunction "IN2_6") (pintype "input"))
    )
    (net (code "63") (name "/REAR-TIMER-IN") (class "Default")
      (node (ref "U$1") (pin "11") (pinfunction "11_11") (pintype "bidirectional"))
      (node (ref "U$7") (pin "3") (pinfunction "OUT2_3") (pintype "output"))
    )
    (net (code "64") (name "/REG5V") (class "Default")
      (node (ref "5VOUTPUT") (pin "2") (pinfunction "KL_2") (pintype "passive"))
      (node (ref "C14") (pin "1") (pinfunction "1_1") (pintype "passive"))
      (node (ref "C16") (pin "1") (pinfunction "1_1") (pintype "passive"))
      (node (ref "C19") (pin "1") (pinfunction "1_1") (pintype "passive"))
      (node (ref "C20") (pin "1") (pinfunction "1_1") (pintype "passive"))
      (node (ref "C31") (pin "1") (pinfunction "1_1") (pintype "passive"))
      (node (ref "OP-AMP") (pin "5") (pinfunction "V+_5") (pintype "power_in"))
      (node (ref "U$2") (pin "8") (pinfunction "VDD2_8") (pintype "power_in"))
      (node (ref "U$5") (pin "16") (pinfunction "VDD2_16") (pintype "bidirectional"))
      (node (ref "U$7") (pin "8") (pinfunction "VDD2_8") (pintype "power_in"))
      (node (ref "VREGULATOR") (pin "2") (pinfunction "VO_2") (pintype "passive"))
    )
    (net (code "65") (name "/REV") (class "Default")
      (node (ref "RC") (pin "3") (pinfunction "3_3") (pintype "passive"))
      (node (ref "U$1") (pin "33") (pinfunction "33_33") (pintype "bidirectional"))
    )
    (net (code "66") (name "/RS-CS") (class "Default")
      (node (ref "RS") (pin "2") (pinfunction "2_2") (pintype "passive"))
      (node (ref "U$1") (pin "52") (pinfunction "52_52") (pintype "bidirectional"))
    )
    (net (code "67") (name "/RX0") (class "Default")
      (node (ref "SPINS") (pin "1") (pinfunction "1_1") (pintype "passive"))
      (node (ref "U$1") (pin "RX0") (pinfunction "RX0_RX0") (pintype "bidirectional"))
    )
    (net (code "68") (name "/RX2") (class "Default")
      (node (ref "SPINS") (pin "3") (pinfunction "3_3") (pintype "passive"))
      (node (ref "U$1") (pin "RX2") (pinfunction "RX2_RX2") (pintype "bidirectional"))
    )
    (net (code "69") (name "/RX3") (class "Default")
      (node (ref "GPS") (pin "2") (pinfunction "2_2") (pintype "passive"))
      (node (ref "U$1") (pin "RX3") (pinfunction "RX3_RX3") (pintype "bidirectional"))
    )
    (net (code "70") (name "/SCK") (class "Default")
      (node (ref "IMU") (pin "5") (pinfunction "5_5") (pintype "passive"))
      (node (ref "RS") (pin "5") (pinfunction "5_5") (pintype "passive"))
      (node (ref "U$1") (pin "SCK_ICSP") (pinfunction "SCK_ICSP_SCK_ICSP") (pintype "bidirectional"))
    )
    (net (code "71") (name "/TX0") (class "Default")
      (node (ref "SPINS") (pin "2") (pinfunction "2_2") (pintype "passive"))
      (node (ref "U$1") (pin "TX0") (pinfunction "TX0_TX0") (pintype "bidirectional"))
    )
    (net (code "72") (name "/TX2") (class "Default")
      (node (ref "SPINS") (pin "4") (pinfunction "4_4") (pintype "passive"))
      (node (ref "U$1") (pin "TX2") (pinfunction "TX2_TX2") (pintype "bidirectional"))
    )
    (net (code "73") (name "/TX3") (class "Default")
      (node (ref "GPS") (pin "3") (pinfunction "3_3") (pintype "passive"))
      (node (ref "U$1") (pin "TX3") (pinfunction "TX3_TX3") (pintype "bidirectional"))
    )
    (net (code "74") (name "Net-(LED1-PadA)") (class "Default")
      (node (ref "LED1") (pin "A") (pinfunction "A_A") (pintype "passive"))
      (node (ref "R1") (pin "2") (pinfunction "2_2") (pintype "passive"))
    )
    (net (code "75") (name "Net-(LED2-PadA)") (class "Default")
      (node (ref "LED2") (pin "A") (pinfunction "A_A") (pintype "passive"))
      (node (ref "R2") (pin "2") (pinfunction "2_2") (pintype "passive"))
    )
    (net (code "76") (name "Net-(LED3-PadA)") (class "Default")
      (node (ref "LED3") (pin "A") (pinfunction "A_A") (pintype "passive"))
      (node (ref "R3") (pin "2") (pinfunction "2_2") (pintype "passive"))
    )
    (net (code "77") (name "Net-(LED4-PadA)") (class "Default")
      (node (ref "LED4") (pin "A") (pinfunction "A_A") (pintype "passive"))
      (node (ref "R19") (pin "2") (pinfunction "2_2") (pintype "passive"))
    )
    (net (code "78") (name "Net-(R2-Pad1)") (class "Default")
      (node (ref "R2") (pin "1") (pinfunction "1_1") (pintype "passive"))
      (node (ref "U$1") (pin "35") (pinfunction "35_35") (pintype "bidirectional"))
    )
    (net (code "79") (name "Net-(R3-Pad1)") (class "Default")
      (node (ref "R3") (pin "1") (pinfunction "1_1") (pintype "passive"))
      (node (ref "U$1") (pin "36") (pinfunction "36_36") (pintype "bidirectional"))
    )
    (net (code "80") (name "Net-(U$5-+IN)") (class "Default")
      (node (ref "R21") (pin "2") (pinfunction "2_2") (pintype "passive"))
      (node (ref "R22") (pin "1") (pinfunction "1_1") (pintype "passive"))
      (node (ref "U$5") (pin "12") (pinfunction "+IN_12") (pintype "bidirectional"))
    )
    (net (code "81") (name "Net-(U$5--IN)") (class "Default")
      (node (ref "U$5") (pin "10") (pinfunction "COMP_10") (pintype "bidirectional"))
      (node (ref "U$5") (pin "11") (pinfunction "-IN_11") (pintype "bidirectional"))
    )
    (net (code "82") (name "Net-(U$5-VREG1)") (class "Default")
      (node (ref "C30") (pin "1") (pinfunction "1_1") (pintype "passive"))
      (node (ref "U$5") (pin "3") (pinfunction "VREG1_3") (pintype "bidirectional"))
    )
    (net (code "83") (name "Net-(U$5-VREG2)") (class "Default")
      (node (ref "C32") (pin "1") (pinfunction "1_1") (pintype "passive"))
      (node (ref "U$5") (pin "14") (pinfunction "VREG2_14") (pintype "bidirectional"))
    )
    (net (code "84") (name "unconnected-(DC-CONV-Pad1)") (class "Default")
      (node (ref "DC-CONV") (pin "1") (pinfunction "1_1") (pintype "passive"))
    )
    (net (code "85") (name "unconnected-(DC-CONV-Pad3)") (class "Default")
      (node (ref "DC-CONV") (pin "3") (pinfunction "3_3") (pintype "passive"))
    )
    (net (code "86") (name "unconnected-(DC-CONV-Pad4)") (class "Default")
      (node (ref "DC-CONV") (pin "4") (pinfunction "4_4") (pintype "passive"))
    )
    (net (code "87") (name "unconnected-(DC-CONV-Pad5)") (class "Default")
      (node (ref "DC-CONV") (pin "5") (pinfunction "5_5") (pintype "passive"))
    )
    (net (code "88") (name "unconnected-(DC-CONV-Pad6)") (class "Default")
      (node (ref "DC-CONV") (pin "6") (pinfunction "6_6") (pintype "passive"))
    )
    (net (code "89") (name "unconnected-(DC-CONV-Pad7)") (class "Default")
      (node (ref "DC-CONV") (pin "7") (pinfunction "7_7") (pintype "passive"))
    )
    (net (code "90") (name "unconnected-(DC-CONV-Pad8)") (class "Default")
      (node (ref "DC-CONV") (pin "8") (pinfunction "8_8") (pintype "passive"))
    )
    (net (code "91") (name "unconnected-(DC-CONV-Pad9)") (class "Default")
      (node (ref "DC-CONV") (pin "9") (pinfunction "9_9") (pintype "passive"))
    )
    (net (code "92") (name "unconnected-(DC-CONV-Pad10)") (class "Default")
      (node (ref "DC-CONV") (pin "10") (pinfunction "10_10") (pintype "passive"))
    )
    (net (code "93") (name "unconnected-(DC-CONV-Pad11)") (class "Default")
      (node (ref "DC-CONV") (pin "11") (pinfunction "11_11") (pintype "passive"))
    )
    (net (code "94") (name "unconnected-(DC-CONV-Pad12)") (class "Default")
      (node (ref "DC-CONV") (pin "12") (pinfunction "12_12") (pintype "passive"))
    )
    (net (code "95") (name "unconnected-(DC-CONV-Pad13)") (class "Default")
      (node (ref "DC-CONV") (pin "13") (pinfunction "13_13") (pintype "passive"))
    )
    (net (code "96") (name "unconnected-(DC-CONV-Pad14)") (class "Default")
      (node (ref "DC-CONV") (pin "14") (pinfunction "14_14") (pintype "passive"))
    )
    (net (code "97") (name "unconnected-(DC-CONV-Pad15)") (class "Default")
      (node (ref "DC-CONV") (pin "15") (pinfunction "15_15") (pintype "passive"))
    )
    (net (code "98") (name "unconnected-(DC-CONV-Pad17)") (class "Default")
      (node (ref "DC-CONV") (pin "17") (pinfunction "17_17") (pintype "passive"))
    )
    (net (code "99") (name "unconnected-(DC-CONV-Pad18)") (class "Default")
      (node (ref "DC-CONV") (pin "18") (pinfunction "18_18") (pintype "passive"))
    )
    (net (code "100") (name "unconnected-(DC-CONV-Pad19)") (class "Default")
      (node (ref "DC-CONV") (pin "19") (pinfunction "19_19") (pintype "passive"))
    )
    (net (code "101") (name "unconnected-(DC-CONV-Pad20)") (class "Default")
      (node (ref "DC-CONV") (pin "20") (pinfunction "20_20") (pintype "passive"))
    )
    (net (code "102") (name "unconnected-(DC-CONV-Pad21)") (class "Default")
      (node (ref "DC-CONV") (pin "21") (pinfunction "21_21") (pintype "passive"))
    )
    (net (code "103") (name "unconnected-(DC-CONV-Pad22)") (class "Default")
      (node (ref "DC-CONV") (pin "22") (pinfunction "22_22") (pintype "passive"))
    )
    (net (code "104") (name "unconnected-(DC-CONV-Pad24)") (class "Default")
      (node (ref "DC-CONV") (pin "24") (pinfunction "24_24") (pintype "passive"))
    )
    (net (code "105") (name "unconnected-(LR1-DOUT-Pad13)") (class "Default")
      (node (ref "LR1") (pin "13") (pinfunction "DOUT_13") (pintype "output"))
    )
    (net (code "106") (name "unconnected-(LR1-~{EN}-Pad12)") (class "Default")
      (node (ref "LR1") (pin "12") (pinfunction "~{EN}_12") (pintype "input"))
    )
    (net (code "107") (name "unconnected-(LR2-DOUT-Pad13)") (class "Default")
      (node (ref "LR2") (pin "13") (pinfunction "DOUT_13") (pintype "output"))
    )
    (net (code "108") (name "unconnected-(LR2-~{EN}-Pad12)") (class "Default")
      (node (ref "LR2") (pin "12") (pinfunction "~{EN}_12") (pintype "input"))
    )
    (net (code "109") (name "unconnected-(U$1-Pad3)") (class "Default")
      (node (ref "U$1") (pin "3") (pinfunction "3_3") (pintype "bidirectional"))
    )
    (net (code "110") (name "unconnected-(U$1-Pad5V_A)") (class "Default")
      (node (ref "U$1") (pin "5V_A") (pinfunction "5V_A_5V_A") (pintype "bidirectional"))
    )
    (net (code "111") (name "unconnected-(U$1-Pad5V_B)") (class "Default")
      (node (ref "U$1") (pin "5V_B") (pinfunction "5V_B_5V_B") (pintype "bidirectional"))
    )
    (net (code "112") (name "unconnected-(U$1-Pad6)") (class "Default")
      (node (ref "U$1") (pin "6") (pinfunction "6_6") (pintype "bidirectional"))
    )
    (net (code "113") (name "unconnected-(U$1-Pad7)") (class "Default")
      (node (ref "U$1") (pin "7") (pinfunction "7_7") (pintype "bidirectional"))
    )
    (net (code "114") (name "unconnected-(U$1-Pad12)") (class "Default")
      (node (ref "U$1") (pin "12") (pinfunction "12_12") (pintype "bidirectional"))
    )
    (net (code "115") (name "unconnected-(U$1-Pad23)") (class "Default")
      (node (ref "U$1") (pin "23") (pinfunction "23_23") (pintype "bidirectional"))
    )
    (net (code "116") (name "unconnected-(U$1-Pad24)") (class "Default")
      (node (ref "U$1") (pin "24") (pinfunction "24_24") (pintype "bidirectional"))
    )
    (net (code "117") (name "unconnected-(U$1-Pad30)") (class "Default")
      (node (ref "U$1") (pin "30") (pinfunction "30_30") (pintype "bidirectional"))
    )
    (net (code "118") (name "unconnected-(U$1-Pad31)") (class "Default")
      (node (ref "U$1") (pin "31") (pinfunction "31_31") (pintype "bidirectional"))
    )
    (net (code "119") (name "unconnected-(U$1-Pad34)") (class "Default")
      (node (ref "U$1") (pin "34") (pinfunction "34_34") (pintype "bidirectional"))
    )
    (net (code "120") (name "unconnected-(U$1-Pad41)") (class "Default")
      (node (ref "U$1") (pin "41") (pinfunction "41_41") (pintype "bidirectional"))
    )
    (net (code "121") (name "unconnected-(U$1-Pad42)") (class "Default")
      (node (ref "U$1") (pin "42") (pinfunction "42_42") (pintype "bidirectional"))
    )
    (net (code "122") (name "unconnected-(U$1-Pad43)") (class "Default")
      (node (ref "U$1") (pin "43") (pinfunction "43_43") (pintype "bidirectional"))
    )
    (net (code "123") (name "unconnected-(U$1-Pad44)") (class "Default")
      (node (ref "U$1") (pin "44") (pinfunction "44_44") (pintype "bidirectional"))
    )
    (net (code "124") (name "unconnected-(U$1-Pad45)") (class "Default")
      (node (ref "U$1") (pin "45") (pinfunction "45_45") (pintype "bidirectional"))
    )
    (net (code "125") (name "unconnected-(U$1-PadA5)") (class "Default")
      (node (ref "U$1") (pin "A5") (pinfunction "A5_A5") (pintype "bidirectional"))
    )
    (net (code "126") (name "unconnected-(U$1-PadA10)") (class "Default")
      (node (ref "U$1") (pin "A10") (pinfunction "A10_A10") (pintype "bidirectional"))
    )
    (net (code "127") (name "unconnected-(U$1-PadAREF)") (class "Default")
      (node (ref "U$1") (pin "AREF") (pinfunction "AREF_AREF") (pintype "bidirectional"))
    )
    (net (code "128") (name "unconnected-(U$1-PadCANRX)") (class "Default")
      (node (ref "U$1") (pin "CANRX") (pinfunction "CANRX_CANRX") (pintype "bidirectional"))
    )
    (net (code "129") (name "unconnected-(U$1-PadCANTX)") (class "Default")
      (node (ref "U$1") (pin "CANTX") (pinfunction "CANTX_CANTX") (pintype "bidirectional"))
    )
    (net (code "130") (name "unconnected-(U$1-PadDAC0)") (class "Default")
      (node (ref "U$1") (pin "DAC0") (pinfunction "DAC0_DAC0") (pintype "bidirectional"))
    )
    (net (code "131") (name "unconnected-(U$1-PadDAC1)") (class "Default")
      (node (ref "U$1") (pin "DAC1") (pinfunction "DAC1_DAC1") (pintype "bidirectional"))
    )
    (net (code "132") (name "unconnected-(U$1-PadGND1)") (class "Default")
      (node (ref "U$1") (pin "GND1") (pinfunction "GND1_GND1") (pintype "bidirectional"))
    )
    (net (code "133") (name "unconnected-(U$1-PadGND_A)") (class "Default")
      (node (ref "U$1") (pin "GND_A") (pinfunction "GND_A_GND_A") (pintype "bidirectional"))
    )
    (net (code "134") (name "unconnected-(U$1-PadGND_B)") (class "Default")
      (node (ref "U$1") (pin "GND_B") (pinfunction "GND_B_GND_B") (pintype "bidirectional"))
    )
    (net (code "135") (name "unconnected-(U$1-PadGND_DEBUG)") (class "Default")
      (node (ref "U$1") (pin "GND_DEBUG") (pinfunction "GND_DEBUG_GND_DEBUG") (pintype "bidirectional"))
    )
    (net (code "136") (name "unconnected-(U$1-PadGND_ICSP)") (class "Default")
      (node (ref "U$1") (pin "GND_ICSP") (pinfunction "GND_ICSP_GND_ICSP") (pintype "bidirectional"))
    )
    (net (code "137") (name "unconnected-(U$1-PadIOREF)") (class "Default")
      (node (ref "U$1") (pin "IOREF") (pinfunction "IOREF_IOREF") (pintype "bidirectional"))
    )
    (net (code "138") (name "unconnected-(U$1-PadNC)") (class "Default")
      (node (ref "U$1") (pin "NC") (pinfunction "NC_NC") (pintype "bidirectional"))
    )
    (net (code "139") (name "unconnected-(U$1-PadRESET)") (class "Default")
      (node (ref "U$1") (pin "RESET") (pinfunction "RESET_RESET") (pintype "bidirectional"))
    )
    (net (code "140") (name "unconnected-(U$1-PadRESET_DEBUG)") (class "Default")
      (node (ref "U$1") (pin "RESET_DEBUG") (pinfunction "RESET_DEBUG_RESET_DEBUG") (pintype "bidirectional"))
    )
    (net (code "141") (name "unconnected-(U$1-PadRESET_ICSP)") (class "Default")
      (node (ref "U$1") (pin "RESET_ICSP") (pinfunction "RESET_ICSP_RESET_ICSP") (pintype "bidirectional"))
    )
    (net (code "142") (name "unconnected-(U$1-PadRX1)") (class "Default")
      (node (ref "U$1") (pin "RX1") (pinfunction "RX1_RX1") (pintype "bidirectional"))
    )
    (net (code "143") (name "unconnected-(U$1-PadSCL)") (class "Default")
      (node (ref "U$1") (pin "SCL") (pinfunction "SCL_SCL") (pintype "bidirectional"))
    )
    (net (code "144") (name "unconnected-(U$1-PadSCL1)") (class "Default")
      (node (ref "U$1") (pin "SCL1") (pinfunction "SCL1_SCL1") (pintype "bidirectional"))
    )
    (net (code "145") (name "unconnected-(U$1-PadSDA)") (class "Default")
      (node (ref "U$1") (pin "SDA") (pinfunction "SDA_SDA") (pintype "bidirectional"))
    )
    (net (code "146") (name "unconnected-(U$1-PadSDA1)") (class "Default")
      (node (ref "U$1") (pin "SDA1") (pinfunction "SDA1_SDA1") (pintype "bidirectional"))
    )
    (net (code "147") (name "unconnected-(U$1-PadSWCLK_DEBUG)") (class "Default")
      (node (ref "U$1") (pin "SWCLK_DEBUG") (pinfunction "SWCLK_DEBUG_SWCLK_DEBUG") (pintype "bidirectional"))
    )
    (net (code "148") (name "unconnected-(U$1-PadSWDIO_DEBUG)") (class "Default")
      (node (ref "U$1") (pin "SWDIO_DEBUG") (pinfunction "SWDIO_DEBUG_SWDIO_DEBUG") (pintype "bidirectional"))
    )
    (net (code "149") (name "unconnected-(U$1-PadTX1)") (class "Default")
      (node (ref "U$1") (pin "TX1") (pinfunction "TX1_TX1") (pintype "bidirectional"))
    )
    (net (code "150") (name "unconnected-(U$5-EAOUT2-Pad6)") (class "Default")
      (node (ref "U$5") (pin "6") (pinfunction "EAOUT2_6") (pintype "bidirectional"))
    )
    (net (code "151") (name "unconnected-(U$5-NC2-Pad5)") (class "Default")
      (node (ref "U$5") (pin "5") (pinfunction "NC2_5") (pintype "bidirectional"))
    )
    (net (code "152") (name "unconnected-(U$5-REFOUT-Pad13)") (class "Default")
      (node (ref "U$5") (pin "13") (pinfunction "REFOUT_13") (pintype "bidirectional"))
    )
    (net (code "153") (name "unconnected-(U$5-REFOUT1-Pad4)") (class "Default")
      (node (ref "U$5") (pin "4") (pinfunction "REFOUT1_4") (pintype "bidirectional"))
    )
  )
)
